# DB_Power-X02.net
KiCad netlist of a schematic drawn in Altium Designer
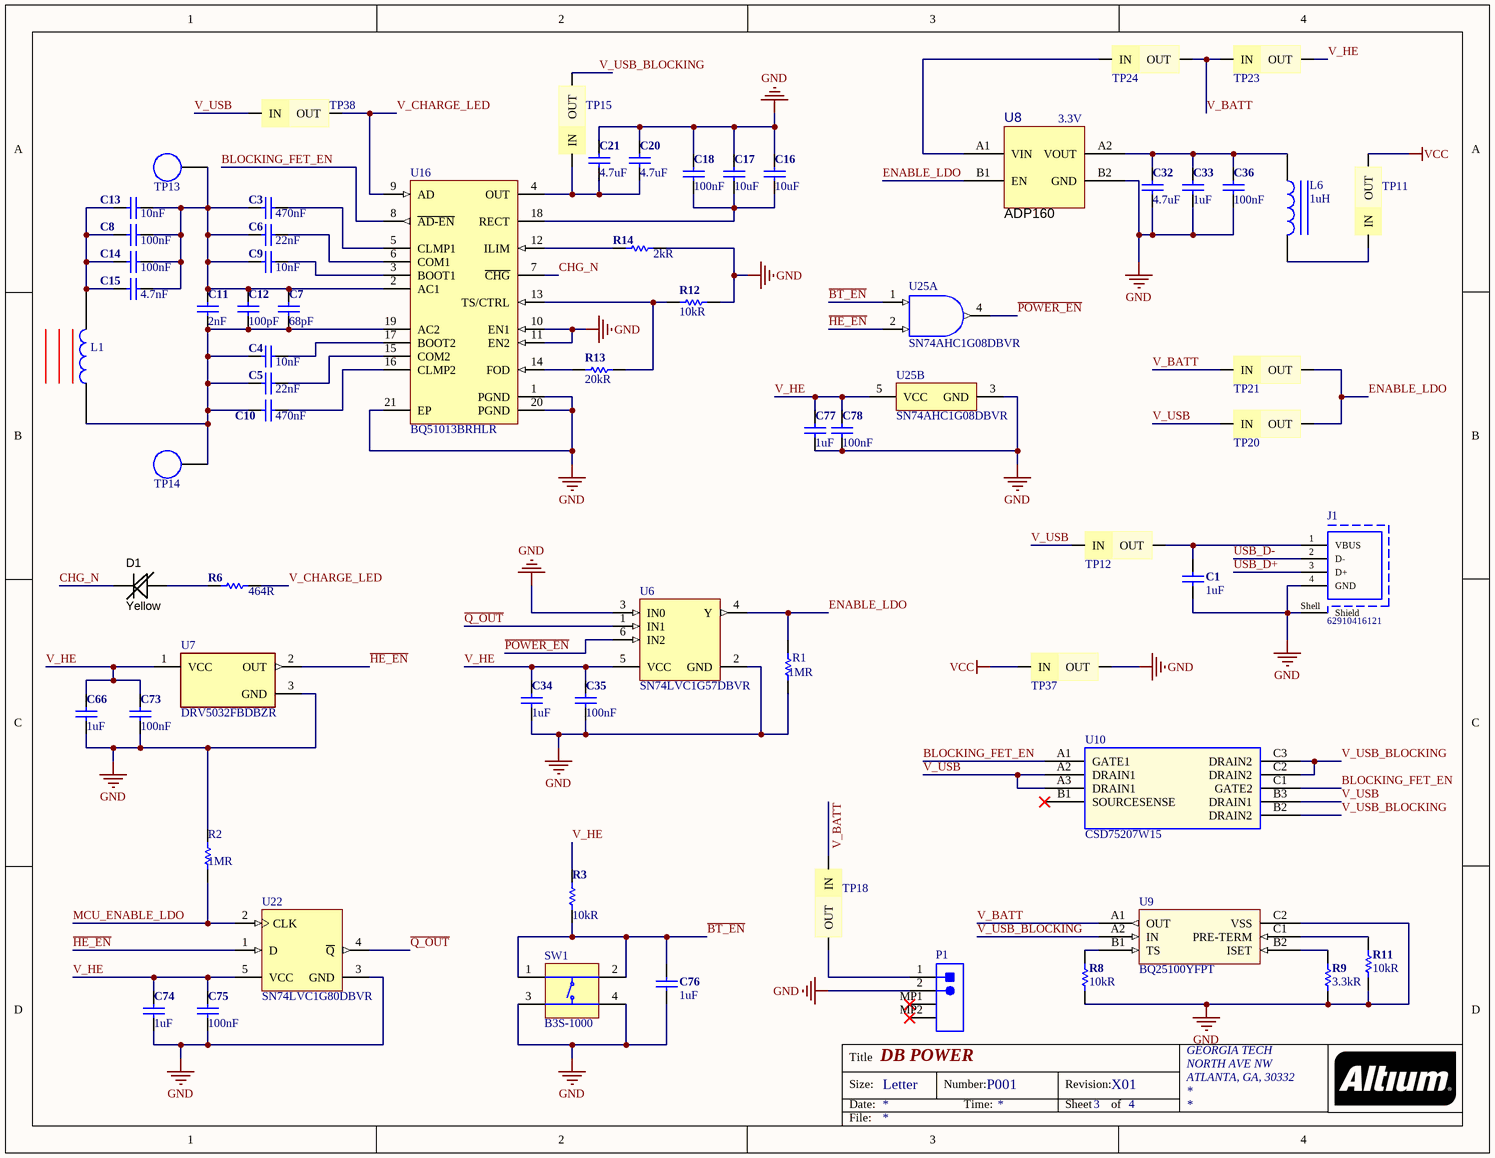
[diagram p0: DB_Power-X02.SchDoc]

(export (version "E")
  (design (tool "Eeschema 10.0.6"))
  (components
    (comp (ref "C1")
      (value "1uF")
      (footprint "C0402")
      (fields
        (field (name "MANUFACTURER") "Yageo")
        (field (name "MANUFACTURER PART NUMBER") "CC0402MRX5R5BB105")
        (field (name "TOLERANCE") "20%")
      )
      (libsource (lib "DB-X01") (part "C-0402(1005)"))
    )
    (comp (ref "C3")
      (value "470nF")
      (footprint "C0402")
      (fields
        (field (name "MANUFACTURER") "Murata")
        (field (name "MANUFACTURER PART NUMBER") "GRT155R61E474ME01D")
        (field (name "TOLERANCE") "20%")
      )
      (libsource (lib "DB-X01") (part "C-0402(1005)"))
    )
    (comp (ref "C4")
      (value "10nF")
      (footprint "C0402")
      (fields
        (field (name "MANUFACTURER") "KEMET")
        (field (name "MANUFACTURER PART NUMBER") "C0402C103J3RACTU")
        (field (name "TOLERANCE") "5%")
      )
      (libsource (lib "DB-X01") (part "C-0402(1005)"))
    )
    (comp (ref "C5")
      (value "22nF")
      (footprint "C0402")
      (fields
        (field (name "MANUFACTURER") "Murata")
        (field (name "MANUFACTURER PART NUMBER") "GRM155R71E223KA61D")
        (field (name "TOLERANCE") "10%")
      )
      (libsource (lib "DB-X01") (part "C-0402(1005)"))
    )
    (comp (ref "C6")
      (value "22nF")
      (footprint "C0402")
      (fields
        (field (name "MANUFACTURER") "Murata")
        (field (name "MANUFACTURER PART NUMBER") "GRM155R71E223KA61D")
        (field (name "TOLERANCE") "10%")
      )
      (libsource (lib "DB-X01") (part "C-0402(1005)"))
    )
    (comp (ref "C7")
      (value "68pF")
      (footprint "C0402")
      (fields
        (field (name "MANUFACTURER") "KEMET")
        (field (name "MANUFACTURER PART NUMBER") "CBR04C680F3GAC")
        (field (name "TOLERANCE") "1%")
      )
      (libsource (lib "DB-X01") (part "C-0402(1005)"))
    )
    (comp (ref "C8")
      (value "100nF")
      (footprint "C0402")
      (fields
        (field (name "MANUFACTURER") "Taiyo Yuden")
        (field (name "MANUFACTURER PART NUMBER") "TMK105BJ104KV-F")
        (field (name "TOLERANCE") "10%")
      )
      (libsource (lib "DB-X01") (part "C-0402(1005)"))
    )
    (comp (ref "C9")
      (value "10nF")
      (footprint "C0402")
      (fields
        (field (name "MANUFACTURER") "KEMET")
        (field (name "MANUFACTURER PART NUMBER") "C0402C103J3RACTU")
        (field (name "TOLERANCE") "5%")
      )
      (libsource (lib "DB-X01") (part "C-0402(1005)"))
    )
    (comp (ref "C10")
      (value "470nF")
      (footprint "C0402")
      (fields
        (field (name "MANUFACTURER") "Murata")
        (field (name "MANUFACTURER PART NUMBER") "GRT155R61E474ME01D")
        (field (name "TOLERANCE") "20%")
      )
      (libsource (lib "DB-X01") (part "C-0402(1005)"))
    )
    (comp (ref "C11")
      (value "2nF")
      (footprint "C0402")
      (fields
        (field (name "MANUFACTURER") "KEMET")
        (field (name "MANUFACTURER PART NUMBER") "C0402C202J3GACTU")
        (field (name "TOLERANCE") "5%")
      )
      (libsource (lib "DB-X01") (part "C-0402(1005)"))
    )
    (comp (ref "C12")
      (value "100pF")
      (footprint "C0402")
      (fields
        (field (name "MANUFACTURER") "KEMET")
        (field (name "MANUFACTURER PART NUMBER") "CBR04C101F3GAC")
        (field (name "TOLERANCE") "1%")
      )
      (libsource (lib "DB-X01") (part "C-0402(1005)"))
    )
    (comp (ref "C13")
      (value "10nF")
      (footprint "C0402")
      (fields
        (field (name "MANUFACTURER") "Yageo")
        (field (name "MANUFACTURER PART NUMBER") "CC0402JRX7R8BB103")
        (field (name "TOLERANCE") "5%")
      )
      (libsource (lib "DB-X01") (part "C-0402(1005)"))
    )
    (comp (ref "C14")
      (value "100nF")
      (footprint "C0402")
      (fields
        (field (name "MANUFACTURER") "Taiyo Yuden")
        (field (name "MANUFACTURER PART NUMBER") "TMK105BJ104KV-F")
        (field (name "TOLERANCE") "10%")
      )
      (libsource (lib "DB-X01") (part "C-0402(1005)"))
    )
    (comp (ref "C15")
      (value "4.7nF")
      (footprint "C0402")
      (fields
        (field (name "MANUFACTURER") "Yageo")
        (field (name "MANUFACTURER PART NUMBER") "CC0402JRX7R8BB472")
        (field (name "TOLERANCE") "5%")
      )
      (libsource (lib "DB-X01") (part "C-0402(1005)"))
    )
    (comp (ref "C16")
      (value "10uF")
      (footprint "C0603")
      (fields
        (field (name "MANUFACTURER") "Murata")
        (field (name "MANUFACTURER PART NUMBER") "GRM188R61E106MA73J")
        (field (name "TOLERANCE") "20%")
      )
      (libsource (lib "DB-X01") (part "C-0603(1608)"))
    )
    (comp (ref "C17")
      (value "10uF")
      (footprint "C0603")
      (fields
        (field (name "MANUFACTURER") "Murata")
        (field (name "MANUFACTURER PART NUMBER") "GRM188R61E106MA73J")
        (field (name "TOLERANCE") "20%")
      )
      (libsource (lib "DB-X01") (part "C-0603(1608)"))
    )
    (comp (ref "C18")
      (value "100nF")
      (footprint "C0603")
      (fields
        (field (name "MANUFACTURER") "Yageo")
        (field (name "MANUFACTURER PART NUMBER") "CC0402ZRY5V8BB104")
        (field (name "TOLERANCE") "80%")
      )
      (libsource (lib "DB-X01") (part "C-0603(1608)"))
    )
    (comp (ref "C20")
      (value "4.7uF")
      (footprint "C0402")
      (description "0402 10 V 4.7 uF ±20% Tolerance X5R Multilayer Ceramic Chip Capacitor")
      (fields
        (field (name "MANUFACTURER") "Murata")
        (field (name "MANUFACTURER PART NUMBER") "GRM155R61A475MEAAD")
      )
      (libsource (lib "DB-X01") (part "C-0402(1005)"))
    )
    (comp (ref "C21")
      (value "4.7uF")
      (footprint "C0402")
      (description "0402 10 V 4.7 uF ±20% Tolerance X5R Multilayer Ceramic Chip Capacitor")
      (fields
        (field (name "MANUFACTURER") "Murata")
        (field (name "MANUFACTURER PART NUMBER") "GRM155R61A475MEAAD")
      )
      (libsource (lib "DB-X01") (part "C-0402(1005)"))
    )
    (comp (ref "C32")
      (value "4.7uF")
      (footprint "C0402")
      (description "0402 10 V 4.7 uF ±20% Tolerance X5R Multilayer Ceramic Chip Capacitor")
      (fields
        (field (name "MANUFACTURER") "Murata")
        (field (name "MANUFACTURER PART NUMBER") "GRM155R61A475MEAAD")
      )
      (libsource (lib "DB-X01") (part "C-0402(1005)"))
    )
    (comp (ref "C33")
      (value "1uF")
      (footprint "C0402")
      (fields
        (field (name "MANUFACTURER") "Yageo")
        (field (name "MANUFACTURER PART NUMBER") "CC0402MRX5R5BB105")
        (field (name "TOLERANCE") "20%")
      )
      (libsource (lib "DB-X01") (part "C-0402(1005)"))
    )
    (comp (ref "C34")
      (value "1uF")
      (footprint "C0402")
      (fields
        (field (name "MANUFACTURER") "Yageo")
        (field (name "MANUFACTURER PART NUMBER") "CC0402MRX5R5BB105")
        (field (name "TOLERANCE") "20%")
      )
      (libsource (lib "DB-X01") (part "C-0402(1005)"))
    )
    (comp (ref "C35")
      (value "100nF")
      (footprint "C0402")
      (fields
        (field (name "MANUFACTURER") "Taiyo Yuden")
        (field (name "MANUFACTURER PART NUMBER") "TMK105BJ104KV-F")
        (field (name "TOLERANCE") "10%")
      )
      (libsource (lib "DB-X01") (part "C-0402(1005)"))
    )
    (comp (ref "C36")
      (value "100nF")
      (footprint "C0402")
      (fields
        (field (name "MANUFACTURER") "Taiyo Yuden")
        (field (name "MANUFACTURER PART NUMBER") "TMK105BJ104KV-F")
        (field (name "TOLERANCE") "10%")
      )
      (libsource (lib "DB-X01") (part "C-0402(1005)"))
    )
    (comp (ref "C66")
      (value "1uF")
      (footprint "C0402")
      (fields
        (field (name "MANUFACTURER") "Yageo")
        (field (name "MANUFACTURER PART NUMBER") "CC0402MRX5R5BB105")
        (field (name "TOLERANCE") "20%")
      )
      (libsource (lib "DB-X01") (part "C-0402(1005)"))
    )
    (comp (ref "C73")
      (value "100nF")
      (footprint "C0402")
      (fields
        (field (name "MANUFACTURER") "Taiyo Yuden")
        (field (name "MANUFACTURER PART NUMBER") "TMK105BJ104KV-F")
        (field (name "TOLERANCE") "10%")
      )
      (libsource (lib "DB-X01") (part "C-0402(1005)"))
    )
    (comp (ref "C74")
      (value "1uF")
      (footprint "C0402")
      (fields
        (field (name "MANUFACTURER") "Yageo")
        (field (name "MANUFACTURER PART NUMBER") "CC0402MRX5R5BB105")
        (field (name "TOLERANCE") "20%")
      )
      (libsource (lib "DB-X01") (part "C-0402(1005)"))
    )
    (comp (ref "C75")
      (value "100nF")
      (footprint "C0402")
      (fields
        (field (name "MANUFACTURER") "Taiyo Yuden")
        (field (name "MANUFACTURER PART NUMBER") "TMK105BJ104KV-F")
        (field (name "TOLERANCE") "10%")
      )
      (libsource (lib "DB-X01") (part "C-0402(1005)"))
    )
    (comp (ref "C76")
      (value "1uF")
      (footprint "C0402")
      (fields
        (field (name "MANUFACTURER") "Yageo")
        (field (name "MANUFACTURER PART NUMBER") "CC0402MRX5R5BB105")
        (field (name "TOLERANCE") "20%")
      )
      (libsource (lib "DB-X01") (part "C-0402(1005)"))
    )
    (comp (ref "C77")
      (value "1uF")
      (footprint "C0402")
      (fields
        (field (name "MANUFACTURER") "Yageo")
        (field (name "MANUFACTURER PART NUMBER") "CC0402MRX5R5BB105")
        (field (name "TOLERANCE") "20%")
      )
      (libsource (lib "DB-X01") (part "C-0402(1005)"))
    )
    (comp (ref "C78")
      (value "100nF")
      (footprint "C0402")
      (fields
        (field (name "MANUFACTURER") "Taiyo Yuden")
        (field (name "MANUFACTURER PART NUMBER") "TMK105BJ104KV-F")
        (field (name "TOLERANCE") "10%")
      )
      (libsource (lib "DB-X01") (part "C-0402(1005)"))
    )
    (comp (ref "D1")
      (value "Yellow")
      (footprint "LED_0402")
      (description "Single Color LED, Super Bright Yellow, Water Clear, 0.8mm")
      (fields
        (field (name "MANUFACTURER") "Kingbright")
        (field (name "MANUFACTURER PART NUMBER") "APHHS1005SYCK")
      )
      (libsource (lib "DB-X01") (part "LED_0402(1005)"))
    )
    (comp (ref "J1")
      (value "62910416121")
      (footprint "62910416121")
      (description "USB 2.0 Type B Receptacle WR-COM, Horizontal, SMT, with Pads and Pegs")
      (fields (field (name "MANUFACTURER") "Wurth Electronics"))
      (libsource (lib "Altium Content Vault") (part "WE-USB-4-1SHLD"))
    )
    (comp (ref "L1")
      (value "WIRELESS CHARGING COIL, RECEIVER")
      (footprint "760308101219")
      (description "General Purpose Inductor, 11.8uH, 10%, 1 Element")
      (fields
        (field (name "MANUFACTURER") "Wurth Electronics")
        (field (name "MANUFACTURER PART NUMBER") "760308101219")
      )
      (libsource (lib "DB-X01") (part "WIRELESS_CHARGING_COIL"))
    )
    (comp (ref "L6")
      (value "1uH")
      (footprint "L0402")
      (description "General Purpose Inductor, 1uH, 20%, 1 Element, Ferrite-Core, SMD, 0402")
      (fields
        (field (name "MANUFACTURER") "TDK")
        (field (name "MANUFACTURER PART NUMBER") "MLZ1005M1R0WT000")
      )
      (libsource (lib "DB-X01") (part "Inductor Iron"))
    )
    (comp (ref "P1")
      (value "B2B-PH-SM4-TB(LF)(SN)")
      (footprint "JST-B2B-PH-SM4-TB-2_V")
      (description "Male Header, Pitch 2 mm, 1 x 2 Position, Height 6.6 mm, RoHS, Tape and Reel")
      (fields (field (name "MANUFACTURER") "JST"))
      (libsource (lib "Altium Content Vault") (part "CN-1P-2M-R2"))
    )
    (comp (ref "R1")
      (value "AC0402FR-071ML")
      (footprint "RESC1005X37X25LL05T10")
      (description "100 ohm resistor")
      (fields
        (field (name "MANUFACTURER") "Yageo")
        (field (name "RESISTANCE") "1MR")
        (field (name "TOLERANCE") "1%")
      )
      (libsource (lib "Altium Content Vault") (part "RES"))
    )
    (comp (ref "R2")
      (value "AC0402FR-071ML")
      (footprint "RESC1005X37X25LL05T10")
      (description "100 ohm resistor")
      (fields
        (field (name "MANUFACTURER") "Yageo")
        (field (name "RESISTANCE") "1MR")
        (field (name "TOLERANCE") "1%")
      )
      (libsource (lib "Altium Content Vault") (part "RES"))
    )
    (comp (ref "R3")
      (value "10kR")
      (footprint "R0402")
      (fields
        (field (name "MANUFACTURER") "Yageo")
        (field (name "MANUFACTURER PART NUMBER") "AC0402FR-0710KL")
        (field (name "TOLERANCE") "1%")
      )
      (libsource (lib "DB-X01") (part "R-0402(1005)"))
    )
    (comp (ref "R6")
      (value "464R")
      (footprint "R0402")
      (fields
        (field (name "MANUFACTURER") "Yageo")
        (field (name "MANUFACTURER PART NUMBER") "RC0402FR-07464RL")
        (field (name "TOLERANCE") "1%")
      )
      (libsource (lib "DB-X01") (part "R-0402(1005)"))
    )
    (comp (ref "R8")
      (value "10kR")
      (footprint "R0402")
      (fields
        (field (name "MANUFACTURER") "Yageo")
        (field (name "MANUFACTURER PART NUMBER") "AC0402FR-0710KL")
        (field (name "TOLERANCE") "1%")
      )
      (libsource (lib "DB-X01") (part "R-0402(1005)"))
    )
    (comp (ref "R9")
      (value "3.3kR")
      (footprint "R0402")
      (fields
        (field (name "MANUFACTURER") "Yageo")
        (field (name "MANUFACTURER PART NUMBER") "AC0402FR-073K3L")
        (field (name "TOLERANCE") "1%")
      )
      (libsource (lib "DB-X01") (part "R-0402(1005)"))
    )
    (comp (ref "R11")
      (value "10kR")
      (footprint "R0402")
      (fields
        (field (name "MANUFACTURER") "Yageo")
        (field (name "MANUFACTURER PART NUMBER") "AC0402FR-0710KL")
        (field (name "TOLERANCE") "1%")
      )
      (libsource (lib "DB-X01") (part "R-0402(1005)"))
    )
    (comp (ref "R12")
      (value "10kR")
      (footprint "R0402")
      (fields
        (field (name "MANUFACTURER") "Yageo")
        (field (name "MANUFACTURER PART NUMBER") "AC0402FR-0710KL")
        (field (name "TOLERANCE") "1%")
      )
      (libsource (lib "DB-X01") (part "R-0402(1005)"))
    )
    (comp (ref "R13")
      (value "20kR")
      (footprint "R0402")
      (fields
        (field (name "MANUFACTURER") "Yageo")
        (field (name "MANUFACTURER PART NUMBER") "AC0402FR-0720KL")
        (field (name "TOLERANCE") "1%")
      )
      (libsource (lib "DB-X01") (part "R-0402(1005)"))
    )
    (comp (ref "R14")
      (value "2kR")
      (footprint "R0402")
      (fields
        (field (name "MANUFACTURER") "Yageo")
        (field (name "MANUFACTURER PART NUMBER") "AC0402FR-072KL")
        (field (name "TOLERANCE") "1%")
      )
      (libsource (lib "DB-X01") (part "R-0402(1005)"))
    )
    (comp (ref "SW1")
      (value "B3S-1000")
      (footprint "OMRON-B3S-1000-4_V")
      (description "Sealed Tactile Switch, SPST-NO, 3 to 24 V, -25 to 70 degC, 4-Pin SMD, RoHS, Bulk")
      (fields (field (name "MANUFACTURER") "Omron") (field (name "MANUFACTURER PART NUMBER") "B3S-1000P"))
      (libsource (lib "Altium Content Vault") (part "SW-SPST-4_A"))
    )
    (comp (ref "TP11")
      (value "JUMPER")
      (footprint "JUMPER")
      (description "SHUNT LP W/HANDLE 2 POS 30AU")
      (fields
        (field (name "MANUFACTURER") "TE Connectivity")
        (field (name "MANUFACTURER PART NUMBER") "8815452")
      )
      (libsource (lib "") (part "JUMPER_1"))
    )
    (comp (ref "TP12")
      (value "JUMPER")
      (footprint "JUMPER")
      (description "SHUNT LP W/HANDLE 2 POS 30AU")
      (fields
        (field (name "MANUFACTURER") "TE Connectivity")
        (field (name "MANUFACTURER PART NUMBER") "8815452")
      )
      (libsource (lib "DB-X01") (part "JUMPER"))
    )
    (comp (ref "TP13")
      (value "S1751-46R")
      (footprint "S1751-46R")
      (description "PC TEST POINT TIN SMD")
      (fields (field (name "MANUFACTURER") "Harwin Inc."))
      (libsource (lib "DB-X01") (part "S1751-46R"))
    )
    (comp (ref "TP14")
      (value "S1751-46R")
      (footprint "S1751-46R")
      (description "PC TEST POINT TIN SMD")
      (fields (field (name "MANUFACTURER") "Harwin Inc."))
      (libsource (lib "DB-X01") (part "S1751-46R"))
    )
    (comp (ref "TP15")
      (value "JUMPER")
      (footprint "JUMPER")
      (description "SHUNT LP W/HANDLE 2 POS 30AU")
      (fields
        (field (name "MANUFACTURER") "TE Connectivity")
        (field (name "MANUFACTURER PART NUMBER") "8815452")
      )
      (libsource (lib "") (part "JUMPER_1"))
    )
    (comp (ref "TP18")
      (value "JUMPER")
      (footprint "JUMPER")
      (description "SHUNT LP W/HANDLE 2 POS 30AU")
      (fields
        (field (name "MANUFACTURER") "TE Connectivity")
        (field (name "MANUFACTURER PART NUMBER") "8815452")
      )
      (libsource (lib "") (part "JUMPER_2"))
    )
    (comp (ref "TP20")
      (value "JUMPER")
      (footprint "JUMPER")
      (description "SHUNT LP W/HANDLE 2 POS 30AU")
      (fields
        (field (name "MANUFACTURER") "TE Connectivity")
        (field (name "MANUFACTURER PART NUMBER") "8815452")
      )
      (libsource (lib "DB-X01") (part "JUMPER"))
    )
    (comp (ref "TP21")
      (value "JUMPER")
      (footprint "JUMPER")
      (description "SHUNT LP W/HANDLE 2 POS 30AU")
      (fields
        (field (name "MANUFACTURER") "TE Connectivity")
        (field (name "MANUFACTURER PART NUMBER") "8815452")
      )
      (libsource (lib "DB-X01") (part "JUMPER"))
    )
    (comp (ref "TP23")
      (value "JUMPER")
      (footprint "JUMPER")
      (description "SHUNT LP W/HANDLE 2 POS 30AU")
      (fields
        (field (name "MANUFACTURER") "TE Connectivity")
        (field (name "MANUFACTURER PART NUMBER") "8815452")
      )
      (libsource (lib "DB-X02") (part "JUMPER"))
    )
    (comp (ref "TP24")
      (value "JUMPER")
      (footprint "JUMPER")
      (description "SHUNT LP W/HANDLE 2 POS 30AU")
      (fields
        (field (name "MANUFACTURER") "TE Connectivity")
        (field (name "MANUFACTURER PART NUMBER") "8815452")
      )
      (libsource (lib "DB-X02") (part "JUMPER"))
    )
    (comp (ref "TP37")
      (value "JUMPER")
      (footprint "JUMPER")
      (description "SHUNT LP W/HANDLE 2 POS 30AU")
      (fields
        (field (name "MANUFACTURER") "TE Connectivity")
        (field (name "MANUFACTURER PART NUMBER") "8815452")
      )
      (libsource (lib "DB-X02") (part "JUMPER"))
    )
    (comp (ref "TP38")
      (value "JUMPER")
      (footprint "JUMPER")
      (description "SHUNT LP W/HANDLE 2 POS 30AU")
      (fields
        (field (name "MANUFACTURER") "TE Connectivity")
        (field (name "MANUFACTURER PART NUMBER") "8815452")
      )
      (libsource (lib "DB-X02") (part "JUMPER"))
    )
    (comp (ref "U6")
      (value "SN74LVC1G57DBVR")
      (footprint "DBV0006A_M")
      (description "CONFIGURABLE MULTIPLE-FUNCTION GATE, DBV0006A, LARGE T&R")
      (fields (field (name "MANUFACTURER") "Texas Instruments"))
      (libsource (lib "Altium Content Vault") (part "TI-SN74XXX1GXX-6"))
    )
    (comp (ref "U7")
      (value "DRV5032FBDBZR")
      (footprint "FP-DBZ0003A-MFG")
      (description "LP HALL 32FBDBZR")
      (fields (field (name "MANUFACTURER") "Texas Instruments"))
      (libsource (lib "Altium Content Vault") (part "2ac151be60cf6bda0d169f73a696793"))
    )
    (comp (ref "U8")
      (value "ADP160")
      (footprint "ADP160")
      (description "Fixed Positive LDO Regulator, 3.3V, 0.195V Dropout, CMOS, PBGA4")
      (fields
        (field (name "MANUFACTURER") "Analog Devices")
        (field (name "MANUFACTURER PART NUMBER") "ADP160ACBZ-3.3-R7")
        (field (name "OUTPUT VOLTAGE") "3.3V")
      )
      (libsource (lib "DB-X01") (part "ADP160-3_3V"))
    )
    (comp (ref "U9")
      (value "BQ25100YFPT")
      (footprint "YZP0006")
      (description "Power Supply Support Circuit")
      (fields (field (name "MANUFACTURER") "Texas Instruments"))
      (libsource (lib "DB-X01") (part "BQ25100YFPT"))
    )
    (comp (ref "U10")
      (value "CSD75207W15")
      (footprint "YZF0009")
      (description "Small Signal Field-Effect Transistor, P-Channel, Metal-oxide Semiconductor FET")
      (fields (field (name "MANUFACTURER") "Texas Instruments"))
      (libsource (lib "DB-X01") (part "CSD75207W15"))
    )
    (comp (ref "U16")
      (value "BQ51013BRHLR")
      (footprint "BQ51013BRHLR")
      (fields (field (name "MANUFACTURER") "Texas Instruments"))
      (libsource (lib "DB-X01") (part "TI-BQ51013B-RHL20"))
    )
    (comp (ref "U22")
      (value "SN74LVC1G80DBVR")
      (footprint "DBV0005A_N")
      (description "Single Positive-Edge-Triggered D-Type Flip-Flop, DBV0005A, LARGE T&R")
      (fields (field (name "MANUFACTURER") "Texas Instruments"))
      (libsource (lib "Altium Content Vault") (part "TI-SN74XXX1G80-5"))
    )
    (comp (ref "U25")
      (value "SN74AHC1G08DBVR")
      (footprint "DBV0005A_N")
      (description "AND Gate, AHC/VHC/H/U/V Series, 1-Func, 2-Input, CMOS, PDSO5")
      (fields (field (name "MANUFACTURER") "Texas Instruments"))
      (libsource (lib "Altium Content Vault") (part "TI-SN74XXX1X08-5"))
    )
  )
  (nets
    (net (code "1") (name "/BLOCKING_FET_EN") (class "Default")
      (node (ref "U10") (pin "A1") (pinfunction "GATE1_A1") (pintype "passive"))
      (node (ref "U10") (pin "C1") (pinfunction "GATE2_C1") (pintype "passive"))
      (node (ref "U16") (pin "8") (pinfunction "~{AD-EN}_8") (pintype "output"))
    )
    (net (code "2") (name "/CHG_N") (class "Default")
      (node (ref "D1") (pin "K") (pinfunction "K_K") (pintype "passive"))
      (node (ref "U16") (pin "7") (pinfunction "~{CHG}_7") (pintype "open_collector"))
    )
    (net (code "3") (name "/ENABLE_LDO") (class "Default")
      (node (ref "R1") (pin "1") (pinfunction "1_1") (pintype "passive"))
      (node (ref "TP20") (pin "2") (pinfunction "OUT_2") (pintype "passive"))
      (node (ref "TP21") (pin "2") (pinfunction "OUT_2") (pintype "passive"))
      (node (ref "U6") (pin "4") (pinfunction "Y_4") (pintype "output"))
      (node (ref "U8") (pin "B1") (pinfunction "EN_B1") (pintype "passive"))
    )
    (net (code "4") (name "/MCU_ENABLE_LDO") (class "Default")
      (node (ref "R2") (pin "1") (pinfunction "1_1") (pintype "passive"))
      (node (ref "U22") (pin "2") (pinfunction "CLK_2") (pintype "input"))
    )
    (net (code "5") (name "/USB_D+") (class "Default")
      (node (ref "J1") (pin "3") (pinfunction "D+_3") (pintype "passive"))
    )
    (net (code "6") (name "/USB_D-") (class "Default")
      (node (ref "J1") (pin "2") (pinfunction "D-_2") (pintype "passive"))
    )
    (net (code "7") (name "/V_BATT") (class "Default")
      (node (ref "TP18") (pin "1") (pinfunction "IN_1") (pintype "passive"))
      (node (ref "TP21") (pin "1") (pinfunction "IN_1") (pintype "passive"))
      (node (ref "TP23") (pin "1") (pinfunction "IN_1") (pintype "passive"))
      (node (ref "TP24") (pin "2") (pinfunction "OUT_2") (pintype "passive"))
      (node (ref "U9") (pin "A1") (pinfunction "OUT_A1") (pintype "output"))
    )
    (net (code "8") (name "/V_CHARGE_LED") (class "Default")
      (node (ref "R6") (pin "2") (pinfunction "2_2") (pintype "passive"))
      (node (ref "TP38") (pin "2") (pinfunction "OUT_2") (pintype "passive"))
      (node (ref "U16") (pin "9") (pinfunction "AD_9") (pintype "input"))
    )
    (net (code "9") (name "/V_HE") (class "Default")
      (node (ref "C34") (pin "1") (pinfunction "1_1") (pintype "passive"))
      (node (ref "C35") (pin "2") (pinfunction "2_2") (pintype "passive"))
      (node (ref "C66") (pin "1") (pinfunction "1_1") (pintype "passive"))
      (node (ref "C73") (pin "2") (pinfunction "2_2") (pintype "passive"))
      (node (ref "C74") (pin "1") (pinfunction "1_1") (pintype "passive"))
      (node (ref "C75") (pin "2") (pinfunction "2_2") (pintype "passive"))
      (node (ref "C77") (pin "1") (pinfunction "1_1") (pintype "passive"))
      (node (ref "C78") (pin "2") (pinfunction "2_2") (pintype "passive"))
      (node (ref "R3") (pin "1") (pinfunction "1_1") (pintype "passive"))
      (node (ref "TP23") (pin "2") (pinfunction "OUT_2") (pintype "passive"))
      (node (ref "U22") (pin "5") (pinfunction "VCC_5") (pintype "power_in"))
      (node (ref "U25") (pin "5") (pinfunction "VCC_5") (pintype "power_in"))
      (node (ref "U6") (pin "5") (pinfunction "VCC_5") (pintype "power_in"))
      (node (ref "U7") (pin "1") (pinfunction "VCC_1") (pintype "power_in"))
    )
    (net (code "10") (name "/V_USB") (class "Default")
      (node (ref "TP12") (pin "1") (pinfunction "IN_1") (pintype "passive"))
      (node (ref "TP20") (pin "1") (pinfunction "IN_1") (pintype "passive"))
      (node (ref "TP38") (pin "1") (pinfunction "IN_1") (pintype "passive"))
      (node (ref "U10") (pin "A2") (pinfunction "DRAIN1_A2") (pintype "passive"))
      (node (ref "U10") (pin "A3") (pinfunction "DRAIN1_A3") (pintype "passive"))
      (node (ref "U10") (pin "B3") (pinfunction "DRAIN1_B3") (pintype "passive"))
    )
    (net (code "11") (name "/V_USB_BLOCKING") (class "Default")
      (node (ref "TP15") (pin "2") (pinfunction "OUT_2") (pintype "passive"))
      (node (ref "U10") (pin "B2") (pinfunction "DRAIN2_B2") (pintype "passive"))
      (node (ref "U10") (pin "C2") (pinfunction "DRAIN2_C2") (pintype "passive"))
      (node (ref "U10") (pin "C3") (pinfunction "DRAIN2_C3") (pintype "passive"))
      (node (ref "U9") (pin "A2") (pinfunction "IN_A2") (pintype "input"))
    )
    (net (code "12") (name "/~{BT_EN}") (class "Default")
      (node (ref "C76") (pin "2") (pinfunction "2_2") (pintype "passive"))
      (node (ref "R3") (pin "2") (pinfunction "2_2") (pintype "passive"))
      (node (ref "SW1") (pin "1") (pinfunction "1_1") (pintype "passive"))
      (node (ref "SW1") (pin "2") (pinfunction "2_2") (pintype "passive"))
      (node (ref "U25") (pin "1") (pinfunction "A_1") (pintype "input"))
    )
    (net (code "13") (name "/~{HE_EN}") (class "Default")
      (node (ref "U22") (pin "1") (pinfunction "D_1") (pintype "input"))
      (node (ref "U25") (pin "2") (pinfunction "B_2") (pintype "input"))
      (node (ref "U7") (pin "2") (pinfunction "OUT_2") (pintype "output"))
    )
    (net (code "14") (name "/~{POWER_EN}") (class "Default")
      (node (ref "U25") (pin "4") (pinfunction "Y_4") (pintype "output"))
      (node (ref "U6") (pin "6") (pinfunction "IN2_6") (pintype "input"))
    )
    (net (code "15") (name "/~{Q_OUT}") (class "Default")
      (node (ref "U22") (pin "4") (pinfunction "~{Q}_4") (pintype "output"))
      (node (ref "U6") (pin "1") (pinfunction "IN1_1") (pintype "input"))
    )
    (net (code "16") (name "GND") (class "Default")
      (node (ref "C1") (pin "2") (pinfunction "2_2") (pintype "passive"))
      (node (ref "C16") (pin "2") (pinfunction "2_2") (pintype "passive"))
      (node (ref "C17") (pin "2") (pinfunction "2_2") (pintype "passive"))
      (node (ref "C18") (pin "2") (pinfunction "2_2") (pintype "passive"))
      (node (ref "C20") (pin "1") (pinfunction "1_1") (pintype "passive"))
      (node (ref "C21") (pin "1") (pinfunction "1_1") (pintype "passive"))
      (node (ref "C32") (pin "2") (pinfunction "2_2") (pintype "passive"))
      (node (ref "C33") (pin "2") (pinfunction "2_2") (pintype "passive"))
      (node (ref "C34") (pin "2") (pinfunction "2_2") (pintype "passive"))
      (node (ref "C35") (pin "1") (pinfunction "1_1") (pintype "passive"))
      (node (ref "C36") (pin "1") (pinfunction "1_1") (pintype "passive"))
      (node (ref "C66") (pin "2") (pinfunction "2_2") (pintype "passive"))
      (node (ref "C73") (pin "1") (pinfunction "1_1") (pintype "passive"))
      (node (ref "C74") (pin "2") (pinfunction "2_2") (pintype "passive"))
      (node (ref "C75") (pin "1") (pinfunction "1_1") (pintype "passive"))
      (node (ref "C76") (pin "1") (pinfunction "1_1") (pintype "passive"))
      (node (ref "C77") (pin "2") (pinfunction "2_2") (pintype "passive"))
      (node (ref "C78") (pin "1") (pinfunction "1_1") (pintype "passive"))
      (node (ref "J1") (pin "4") (pinfunction "GND_4") (pintype "passive"))
      (node (ref "J1") (pin "Shell") (pinfunction "Shield_Shell") (pintype "passive"))
      (node (ref "P1") (pin "2") (pinfunction "2_2") (pintype "passive"))
      (node (ref "R1") (pin "2") (pinfunction "2_2") (pintype "passive"))
      (node (ref "R11") (pin "1") (pinfunction "1_1") (pintype "passive"))
      (node (ref "R12") (pin "2") (pinfunction "2_2") (pintype "passive"))
      (node (ref "R14") (pin "2") (pinfunction "2_2") (pintype "passive"))
      (node (ref "R2") (pin "2") (pinfunction "2_2") (pintype "passive"))
      (node (ref "R8") (pin "1") (pinfunction "1_1") (pintype "passive"))
      (node (ref "R9") (pin "1") (pinfunction "1_1") (pintype "passive"))
      (node (ref "SW1") (pin "3") (pinfunction "3_3") (pintype "passive"))
      (node (ref "SW1") (pin "4") (pinfunction "4_4") (pintype "passive"))
      (node (ref "TP37") (pin "2") (pinfunction "OUT_2") (pintype "passive"))
      (node (ref "U16") (pin "1") (pinfunction "PGND_1") (pintype "power_in"))
      (node (ref "U16") (pin "10") (pinfunction "EN1_10") (pintype "input"))
      (node (ref "U16") (pin "11") (pinfunction "EN2_11") (pintype "input"))
      (node (ref "U16") (pin "20") (pinfunction "PGND_20") (pintype "power_in"))
      (node (ref "U16") (pin "21") (pinfunction "EP_21") (pintype "passive"))
      (node (ref "U22") (pin "3") (pinfunction "GND_3") (pintype "power_in"))
      (node (ref "U25") (pin "3") (pinfunction "GND_3") (pintype "power_in"))
      (node (ref "U6") (pin "2") (pinfunction "GND_2") (pintype "power_in"))
      (node (ref "U6") (pin "3") (pinfunction "IN0_3") (pintype "input"))
      (node (ref "U7") (pin "3") (pinfunction "GND_3") (pintype "power_in"))
      (node (ref "U8") (pin "B2") (pinfunction "GND_B2") (pintype "passive"))
      (node (ref "U9") (pin "C2") (pinfunction "VSS_C2") (pintype "power_in"))
    )
    (net (code "17") (name "Net-(C13-Pad1)") (class "Default")
      (node (ref "C13") (pin "1") (pinfunction "1_1") (pintype "passive"))
      (node (ref "C14") (pin "1") (pinfunction "1_1") (pintype "passive"))
      (node (ref "C15") (pin "1") (pinfunction "1_1") (pintype "passive"))
      (node (ref "C8") (pin "1") (pinfunction "1_1") (pintype "passive"))
      (node (ref "L1") (pin "2") (pinfunction "2_2") (pintype "passive"))
    )
    (net (code "18") (name "Net-(D1-PadA)") (class "Default")
      (node (ref "D1") (pin "A") (pinfunction "A_A") (pintype "passive"))
      (node (ref "R6") (pin "1") (pinfunction "1_1") (pintype "passive"))
    )
    (net (code "19") (name "Net-(J1-VBUS)") (class "Default")
      (node (ref "C1") (pin "1") (pinfunction "1_1") (pintype "passive"))
      (node (ref "J1") (pin "1") (pinfunction "VBUS_1") (pintype "passive"))
      (node (ref "TP12") (pin "2") (pinfunction "OUT_2") (pintype "passive"))
    )
    (net (code "20") (name "Net-(TP11-IN)") (class "Default")
      (node (ref "L6") (pin "2") (pinfunction "2_2") (pintype "passive"))
      (node (ref "TP11") (pin "1") (pinfunction "IN_1") (pintype "passive"))
    )
    (net (code "21") (name "Net-(TP15-IN)") (class "Default")
      (node (ref "C20") (pin "2") (pinfunction "2_2") (pintype "passive"))
      (node (ref "C21") (pin "2") (pinfunction "2_2") (pintype "passive"))
      (node (ref "TP15") (pin "1") (pinfunction "IN_1") (pintype "passive"))
      (node (ref "U16") (pin "4") (pinfunction "OUT_4") (pintype "power_in"))
    )
    (net (code "22") (name "Net-(TP18-OUT)") (class "Default")
      (node (ref "P1") (pin "1") (pinfunction "1_1") (pintype "passive"))
      (node (ref "TP18") (pin "2") (pinfunction "OUT_2") (pintype "passive"))
    )
    (net (code "23") (name "Net-(TP24-IN)") (class "Default")
      (node (ref "TP24") (pin "1") (pinfunction "IN_1") (pintype "passive"))
      (node (ref "U8") (pin "A1") (pinfunction "VIN_A1") (pintype "passive"))
    )
    (net (code "24") (name "Net-(U8-VOUT)") (class "Default")
      (node (ref "C32") (pin "1") (pinfunction "1_1") (pintype "passive"))
      (node (ref "C33") (pin "1") (pinfunction "1_1") (pintype "passive"))
      (node (ref "C36") (pin "2") (pinfunction "2_2") (pintype "passive"))
      (node (ref "L6") (pin "1") (pinfunction "1_1") (pintype "passive"))
      (node (ref "U8") (pin "A2") (pinfunction "VOUT_A2") (pintype "passive"))
    )
    (net (code "25") (name "Net-(U9-ISET)") (class "Default")
      (node (ref "R9") (pin "2") (pinfunction "2_2") (pintype "passive"))
      (node (ref "U9") (pin "B2") (pinfunction "ISET_B2") (pintype "input"))
    )
    (net (code "26") (name "Net-(U9-PRE-TERM)") (class "Default")
      (node (ref "R11") (pin "2") (pinfunction "2_2") (pintype "passive"))
      (node (ref "U9") (pin "C1") (pinfunction "PRE-TERM_C1") (pintype "input"))
    )
    (net (code "27") (name "Net-(U9-TS)") (class "Default")
      (node (ref "R8") (pin "2") (pinfunction "2_2") (pintype "passive"))
      (node (ref "U9") (pin "B1") (pinfunction "TS_B1") (pintype "input"))
    )
    (net (code "28") (name "Net-(U16-AC1)") (class "Default")
      (node (ref "C11") (pin "1") (pinfunction "1_1") (pintype "passive"))
      (node (ref "C12") (pin "1") (pinfunction "1_1") (pintype "passive"))
      (node (ref "C13") (pin "2") (pinfunction "2_2") (pintype "passive"))
      (node (ref "C14") (pin "2") (pinfunction "2_2") (pintype "passive"))
      (node (ref "C15") (pin "2") (pinfunction "2_2") (pintype "passive"))
      (node (ref "C3") (pin "1") (pinfunction "1_1") (pintype "passive"))
      (node (ref "C6") (pin "1") (pinfunction "1_1") (pintype "passive"))
      (node (ref "C7") (pin "1") (pinfunction "1_1") (pintype "passive"))
      (node (ref "C8") (pin "2") (pinfunction "2_2") (pintype "passive"))
      (node (ref "C9") (pin "1") (pinfunction "1_1") (pintype "passive"))
      (node (ref "TP13") (pin "1") (pinfunction "1_1") (pintype "passive"))
      (node (ref "U16") (pin "2") (pinfunction "AC1_2") (pintype "power_in"))
    )
    (net (code "29") (name "Net-(U16-AC2)") (class "Default")
      (node (ref "C10") (pin "1") (pinfunction "1_1") (pintype "passive"))
      (node (ref "C11") (pin "2") (pinfunction "2_2") (pintype "passive"))
      (node (ref "C12") (pin "2") (pinfunction "2_2") (pintype "passive"))
      (node (ref "C4") (pin "1") (pinfunction "1_1") (pintype "passive"))
      (node (ref "C5") (pin "1") (pinfunction "1_1") (pintype "passive"))
      (node (ref "C7") (pin "2") (pinfunction "2_2") (pintype "passive"))
      (node (ref "L1") (pin "1") (pinfunction "1_1") (pintype "passive"))
      (node (ref "TP14") (pin "1") (pinfunction "1_1") (pintype "passive"))
      (node (ref "U16") (pin "19") (pinfunction "AC2_19") (pintype "power_in"))
    )
    (net (code "30") (name "Net-(U16-BOOT1)") (class "Default")
      (node (ref "C9") (pin "2") (pinfunction "2_2") (pintype "passive"))
      (node (ref "U16") (pin "3") (pinfunction "BOOT1_3") (pintype "passive"))
    )
    (net (code "31") (name "Net-(U16-BOOT2)") (class "Default")
      (node (ref "C4") (pin "2") (pinfunction "2_2") (pintype "passive"))
      (node (ref "U16") (pin "17") (pinfunction "BOOT2_17") (pintype "passive"))
    )
    (net (code "32") (name "Net-(U16-CLMP1)") (class "Default")
      (node (ref "C3") (pin "2") (pinfunction "2_2") (pintype "passive"))
      (node (ref "U16") (pin "5") (pinfunction "CLMP1_5") (pintype "open_collector"))
    )
    (net (code "33") (name "Net-(U16-CLMP2)") (class "Default")
      (node (ref "C10") (pin "2") (pinfunction "2_2") (pintype "passive"))
      (node (ref "U16") (pin "16") (pinfunction "CLMP2_16") (pintype "open_collector"))
    )
    (net (code "34") (name "Net-(U16-COM1)") (class "Default")
      (node (ref "C6") (pin "2") (pinfunction "2_2") (pintype "passive"))
      (node (ref "U16") (pin "6") (pinfunction "COM1_6") (pintype "open_collector"))
    )
    (net (code "35") (name "Net-(U16-COM2)") (class "Default")
      (node (ref "C5") (pin "2") (pinfunction "2_2") (pintype "passive"))
      (node (ref "U16") (pin "15") (pinfunction "COM2_15") (pintype "open_collector"))
    )
    (net (code "36") (name "Net-(U16-FOD)") (class "Default")
      (node (ref "R13") (pin "1") (pinfunction "1_1") (pintype "passive"))
      (node (ref "U16") (pin "14") (pinfunction "FOD_14") (pintype "input"))
    )
    (net (code "37") (name "Net-(U16-ILIM)") (class "Default")
      (node (ref "R14") (pin "1") (pinfunction "1_1") (pintype "passive"))
      (node (ref "U16") (pin "12") (pinfunction "ILIM_12") (pintype "input"))
    )
    (net (code "38") (name "Net-(U16-RECT)") (class "Default")
      (node (ref "C16") (pin "1") (pinfunction "1_1") (pintype "passive"))
      (node (ref "C17") (pin "1") (pinfunction "1_1") (pintype "passive"))
      (node (ref "C18") (pin "1") (pinfunction "1_1") (pintype "passive"))
      (node (ref "U16") (pin "18") (pinfunction "RECT_18") (pintype "passive"))
    )
    (net (code "39") (name "Net-(U16-TS{slash}CTRL)") (class "Default")
      (node (ref "R12") (pin "1") (pinfunction "1_1") (pintype "passive"))
      (node (ref "R13") (pin "2") (pinfunction "2_2") (pintype "passive"))
      (node (ref "U16") (pin "13") (pinfunction "TS/CTRL_13") (pintype "input"))
    )
    (net (code "40") (name "VCC") (class "Default")
      (node (ref "TP11") (pin "2") (pinfunction "OUT_2") (pintype "passive"))
      (node (ref "TP37") (pin "1") (pinfunction "IN_1") (pintype "passive"))
    )
    (net (code "41") (name "unconnected-(P1-PadMP1)") (class "Default")
      (node (ref "P1") (pin "MP1") (pinfunction "MP1_MP1") (pintype "passive+no_connect"))
    )
    (net (code "42") (name "unconnected-(P1-PadMP2)") (class "Default")
      (node (ref "P1") (pin "MP2") (pinfunction "MP2_MP2") (pintype "passive+no_connect"))
    )
    (net (code "43") (name "unconnected-(U10-SOURCESENSE-PadB1)") (class "Default")
      (node (ref "U10") (pin "B1") (pinfunction "SOURCESENSE_B1") (pintype "passive+no_connect"))
    )
  )
)
